# Opto-coupler_SMD.net
KiCad netlist of a schematic drawn in EAGLE
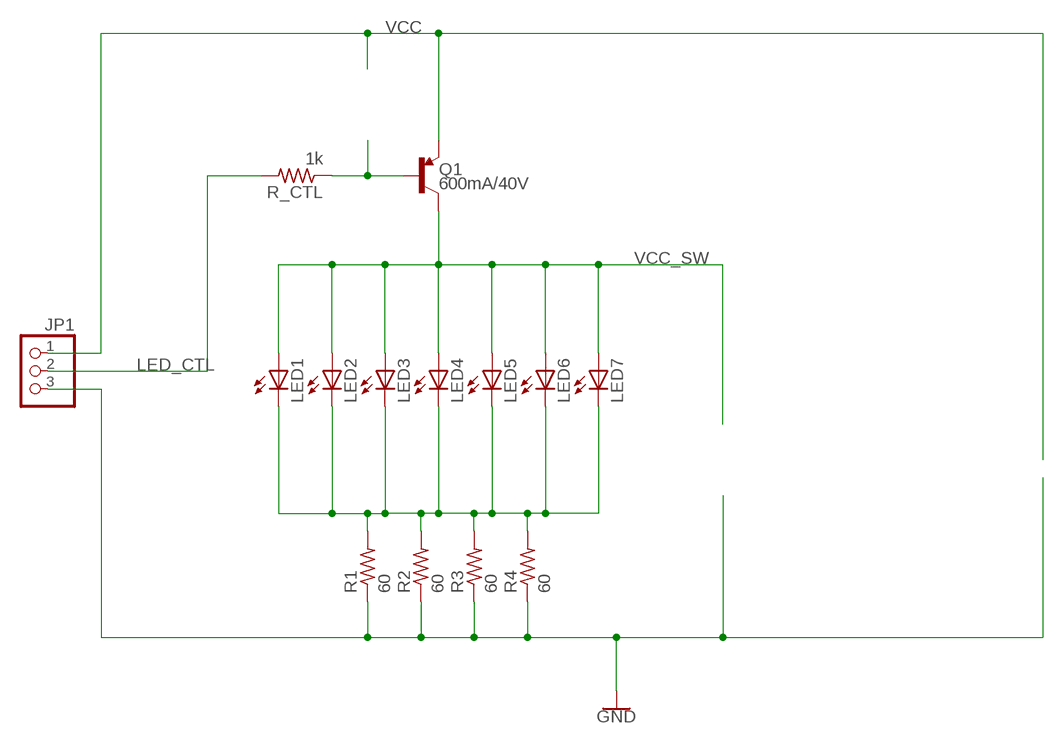
[diagram p0: schematic, sheet 1]

(export (version "E")
  (design (tool "Eeschema 10.0.6"))
  (components
    (comp (ref "JP1")
      (value "PINHD-1X3")
      (footprint "eagle-import:1X03")
      (libsource (lib "eagle-import") (part "PINHD-1X3"))
    )
    (comp (ref "LED1")
      (value "LEDCHIPLED_0603")
      (footprint "eagle-import:CHIPLED_0603")
      (libsource (lib "eagle-import") (part "LEDCHIPLED_0603"))
    )
    (comp (ref "LED2")
      (value "LEDCHIPLED_0603")
      (footprint "eagle-import:CHIPLED_0603")
      (libsource (lib "eagle-import") (part "LEDCHIPLED_0603"))
    )
    (comp (ref "LED3")
      (value "LEDCHIPLED_0603")
      (footprint "eagle-import:CHIPLED_0603")
      (libsource (lib "eagle-import") (part "LEDCHIPLED_0603"))
    )
    (comp (ref "LED4")
      (value "LEDCHIPLED_0603")
      (footprint "eagle-import:CHIPLED_0603")
      (libsource (lib "eagle-import") (part "LEDCHIPLED_0603"))
    )
    (comp (ref "LED5")
      (value "LEDCHIPLED_0603")
      (footprint "eagle-import:CHIPLED_0603")
      (libsource (lib "eagle-import") (part "LEDCHIPLED_0603"))
    )
    (comp (ref "LED6")
      (value "LEDCHIPLED_0603")
      (footprint "eagle-import:CHIPLED_0603")
      (libsource (lib "eagle-import") (part "LEDCHIPLED_0603"))
    )
    (comp (ref "LED7")
      (value "LEDCHIPLED_0603")
      (footprint "eagle-import:CHIPLED_0603")
      (libsource (lib "eagle-import") (part "LEDCHIPLED_0603"))
    )
    (comp (ref "Q1")
      (value "600mA/40V")
      (footprint "eagle-import:SOT23-3")
      (libsource (lib "eagle-import") (part "TRANS_PNP-MMBT4403"))
    )
    (comp (ref "R1")
      (value "60")
      (footprint "eagle-import:R0603")
      (libsource (lib "eagle-import") (part "R-US_R0603"))
    )
    (comp (ref "R2")
      (value "60")
      (footprint "eagle-import:R0603")
      (libsource (lib "eagle-import") (part "R-US_R0603"))
    )
    (comp (ref "R3")
      (value "60")
      (footprint "eagle-import:R0603")
      (libsource (lib "eagle-import") (part "R-US_R0603"))
    )
    (comp (ref "R4")
      (value "60")
      (footprint "eagle-import:R0603")
      (libsource (lib "eagle-import") (part "R-US_R0603"))
    )
    (comp (ref "R_CTL")
      (value "1k")
      (footprint "eagle-import:R0603")
      (libsource (lib "eagle-import") (part "R-US_R0603"))
    )
  )
  (nets
    (net (code "1") (name "/LED_CTL") (class "Default")
      (node (ref "JP1") (pin "2") (pinfunction "2_2") (pintype "passive"))
      (node (ref "R_CTL") (pin "2") (pinfunction "2_2") (pintype "passive"))
    )
    (net (code "2") (name "/VCC") (class "Default")
      (node (ref "JP1") (pin "1") (pinfunction "1_1") (pintype "passive"))
      (node (ref "Q1") (pin "2") (pinfunction "E_2") (pintype "passive"))
    )
    (net (code "3") (name "/VCC_SW") (class "Default")
      (node (ref "LED1") (pin "A") (pinfunction "A_A") (pintype "passive"))
      (node (ref "LED2") (pin "A") (pinfunction "A_A") (pintype "passive"))
      (node (ref "LED3") (pin "A") (pinfunction "A_A") (pintype "passive"))
      (node (ref "LED4") (pin "A") (pinfunction "A_A") (pintype "passive"))
      (node (ref "LED5") (pin "A") (pinfunction "A_A") (pintype "passive"))
      (node (ref "LED6") (pin "A") (pinfunction "A_A") (pintype "passive"))
      (node (ref "LED7") (pin "A") (pinfunction "A_A") (pintype "passive"))
      (node (ref "Q1") (pin "3") (pinfunction "C_3") (pintype "passive"))
    )
    (net (code "4") (name "GND") (class "Default")
      (node (ref "JP1") (pin "3") (pinfunction "3_3") (pintype "passive"))
      (node (ref "R1") (pin "1") (pinfunction "1_1") (pintype "passive"))
      (node (ref "R2") (pin "1") (pinfunction "1_1") (pintype "passive"))
      (node (ref "R3") (pin "1") (pinfunction "1_1") (pintype "passive"))
      (node (ref "R4") (pin "1") (pinfunction "1_1") (pintype "passive"))
    )
    (net (code "5") (name "Net-(LED1-PadC)") (class "Default")
      (node (ref "LED1") (pin "C") (pinfunction "C_C") (pintype "passive"))
      (node (ref "LED2") (pin "C") (pinfunction "C_C") (pintype "passive"))
      (node (ref "LED3") (pin "C") (pinfunction "C_C") (pintype "passive"))
      (node (ref "LED4") (pin "C") (pinfunction "C_C") (pintype "passive"))
      (node (ref "LED5") (pin "C") (pinfunction "C_C") (pintype "passive"))
      (node (ref "LED6") (pin "C") (pinfunction "C_C") (pintype "passive"))
      (node (ref "LED7") (pin "C") (pinfunction "C_C") (pintype "passive"))
      (node (ref "R1") (pin "2") (pinfunction "2_2") (pintype "passive"))
      (node (ref "R2") (pin "2") (pinfunction "2_2") (pintype "passive"))
      (node (ref "R3") (pin "2") (pinfunction "2_2") (pintype "passive"))
      (node (ref "R4") (pin "2") (pinfunction "2_2") (pintype "passive"))
    )
    (net (code "6") (name "Net-(Q1-B)") (class "Default")
      (node (ref "Q1") (pin "1") (pinfunction "B_1") (pintype "passive"))
      (node (ref "R_CTL") (pin "1") (pinfunction "1_1") (pintype "passive"))
    )
  )
)
